# OTGW01_psu_rev1.net
KiCad netlist of a schematic drawn in Altium Designer
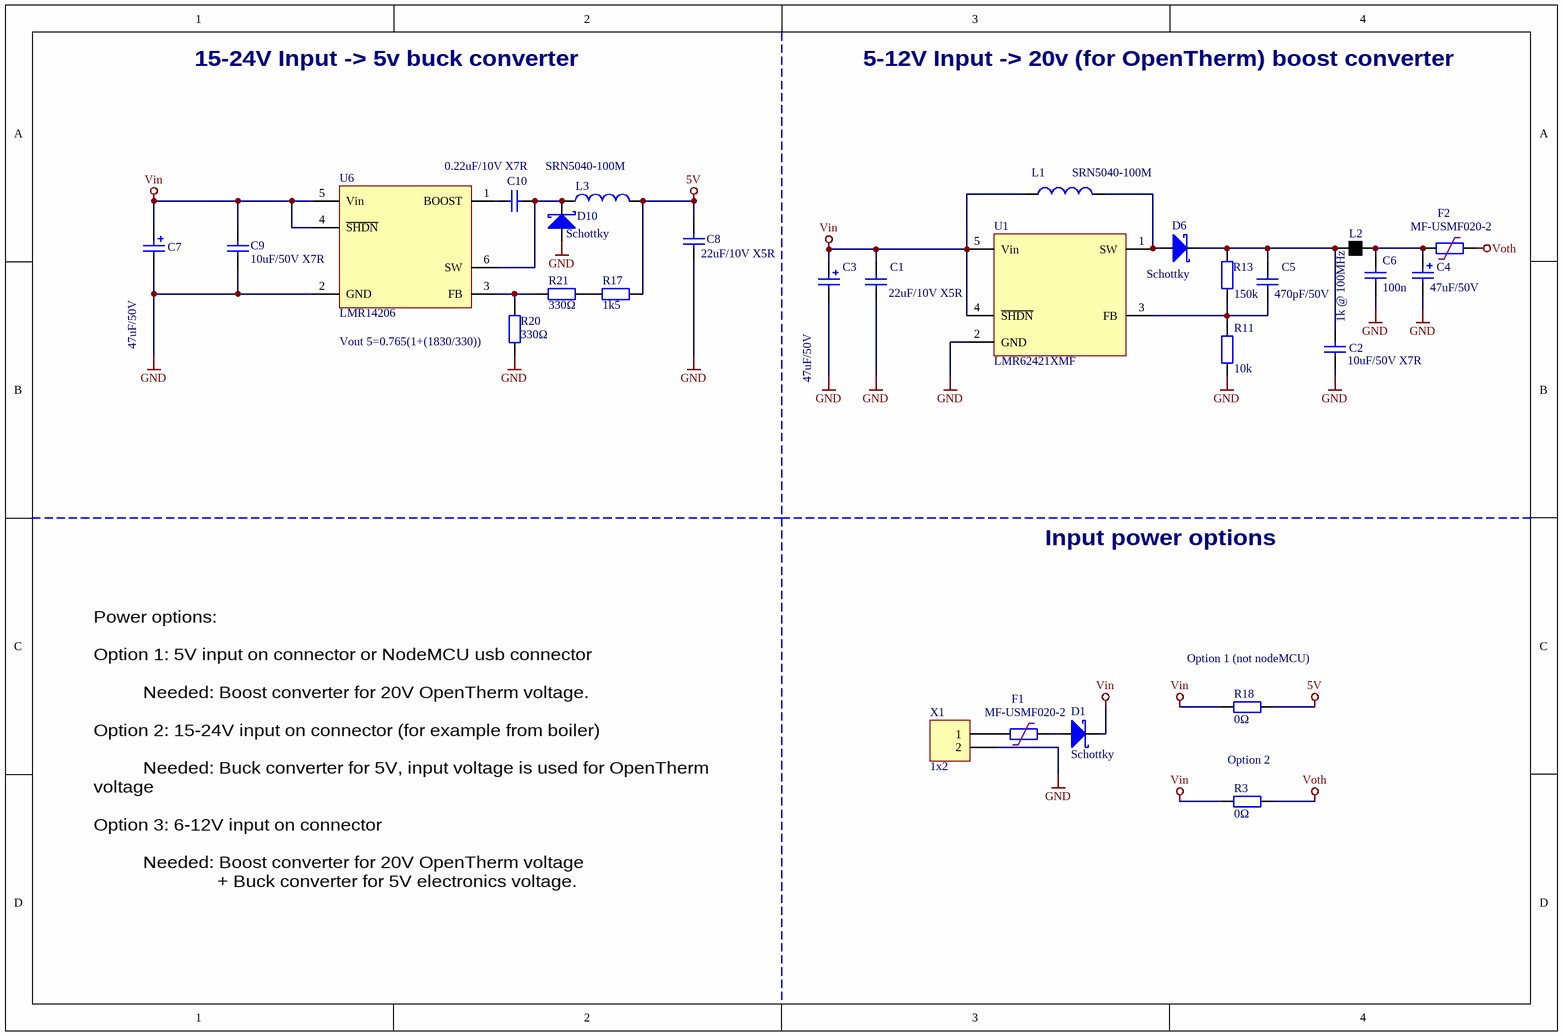
[diagram p0: OTGW01_psu_rev1.SchDoc]

(export (version "E")
  (design (tool "Eeschema 10.0.6"))
  (components
    (comp (ref "C1")
      (value "22uF/10V X5R")
      (footprint "1210")
      (description "Capacitor Non Polarized")
      (libsource (lib "OTGW01_rev1") (part "C"))
    )
    (comp (ref "C2")
      (value "10uF/50V X7R")
      (footprint "1210")
      (description "Capacitor Non Polarized")
      (libsource (lib "OTGW01_rev1") (part "C"))
    )
    (comp (ref "C3")
      (value "47uF/50V")
      (footprint "C_D8")
      (description "Capacitor Polarized")
      (libsource (lib "OTGW01_rev1") (part "C_POL"))
    )
    (comp (ref "C4")
      (value "47uF/50V")
      (footprint "C_D8")
      (description "Capacitor Polarized")
      (libsource (lib "OTGW01_rev1") (part "C_POL"))
    )
    (comp (ref "C5")
      (value "470pF/50V")
      (footprint "0805")
      (description "Capacitor Non Polarized")
      (libsource (lib "OTGW01_rev1") (part "C"))
    )
    (comp (ref "C6")
      (value "100n")
      (footprint "0805")
      (description "Capacitor Non Polarized")
      (libsource (lib "sap") (part "C"))
    )
    (comp (ref "C7")
      (value "47uF/50V")
      (footprint "C_D8")
      (description "Capacitor Polarized")
      (libsource (lib "OTGW01_rev1") (part "C_POL"))
    )
    (comp (ref "C8")
      (value "22uF/10V X5R")
      (footprint "1210")
      (description "Capacitor Non Polarized")
      (libsource (lib "OTGW01_rev1") (part "C"))
    )
    (comp (ref "C9")
      (value "10uF/50V X7R")
      (footprint "1210")
      (description "Capacitor Non Polarized")
      (libsource (lib "OTGW01_rev1") (part "C"))
    )
    (comp (ref "C10")
      (value "0.22uF/10V X7R")
      (footprint "0805")
      (description "Capacitor Non Polarized")
      (libsource (lib "OTGW01_rev1") (part "C"))
    )
    (comp (ref "D1") (value "Schottky") (footprint "SOD123") (libsource (lib "OTGW01_rev1") (part "D_S")))
    (comp (ref "D6") (value "Schottky") (footprint "SOD123") (libsource (lib "OTGW01_rev1") (part "D_S")))
    (comp (ref "D10") (value "Schottky") (footprint "SOD123") (libsource (lib "OTGW01_rev1") (part "D_S")))
    (comp (ref "F1") (value "MF-USMF020-2") (footprint "1210F") (libsource (lib "OTGW01_rev1") (part "PPTC")))
    (comp (ref "F2") (value "MF-USMF020-2") (footprint "1210F") (libsource (lib "OTGW01_rev1") (part "PPTC")))
    (comp (ref "L1")
      (value "SRN5040-100M")
      (footprint "SRN5040")
      (description "L")
      (libsource (lib "OTGW01_rev1") (part "L"))
    )
    (comp (ref "L2")
      (value "1k @ 100MHz")
      (footprint "0805")
      (libsource (lib "OTGW01_rev1") (part "Ferrite"))
    )
    (comp (ref "L3")
      (value "SRN5040-100M")
      (footprint "SRN5040")
      (description "L")
      (libsource (lib "OTGW01_rev1") (part "L"))
    )
    (comp (ref "R3")
      (value "0Ω")
      (footprint "0805")
      (description "Resistor")
      (libsource (lib "") (part "R_1"))
    )
    (comp (ref "R11")
      (value "10k")
      (footprint "0805")
      (description "Resistor")
      (libsource (lib "OTGW01_rev1") (part "R"))
    )
    (comp (ref "R13")
      (value "150k")
      (footprint "0805")
      (description "Resistor")
      (libsource (lib "OTGW01_rev1") (part "R"))
    )
    (comp (ref "R17")
      (value "1k5")
      (footprint "0805")
      (description "Resistor")
      (libsource (lib "") (part "R_1"))
    )
    (comp (ref "R18")
      (value "0Ω")
      (footprint "0805")
      (description "Resistor")
      (libsource (lib "") (part "R_1"))
    )
    (comp (ref "R20")
      (value "330Ω")
      (footprint "0805")
      (description "Resistor")
      (libsource (lib "") (part "R_2"))
    )
    (comp (ref "R21")
      (value "330Ω")
      (footprint "0805")
      (description "Resistor")
      (libsource (lib "") (part "R_1"))
    )
    (comp (ref "U1")
      (value "LMR62421XMF")
      (footprint "SOT23_5")
      (libsource (lib "OTGW01_rev1") (part "LMR62421XMF"))
    )
    (comp (ref "U6")
      (value "LMR14206")
      (footprint "SOT23_6")
      (libsource (lib "OTGW01_rev1") (part "LMR14206"))
    )
    (comp (ref "X1")
      (value "1x2")
      (footprint "Terminal_2x3.5mm")
      (libsource (lib "OTGW01_rev1") (part "CON_1x2"))
    )
  )
  (nets
    (net (code "1") (name "5V") (class "Default")
      (node (ref "C8") (pin "2") (pinfunction "2_2") (pintype "passive"))
      (node (ref "L3") (pin "2") (pinfunction "2_2") (pintype "passive"))
      (node (ref "R17") (pin "2") (pinfunction "2_2") (pintype "passive"))
      (node (ref "R18") (pin "2") (pinfunction "2_2") (pintype "passive"))
    )
    (net (code "2") (name "GND") (class "Default")
      (node (ref "C1") (pin "1") (pinfunction "1_1") (pintype "passive"))
      (node (ref "C2") (pin "2") (pinfunction "2_2") (pintype "passive"))
      (node (ref "C3") (pin "2") (pinfunction "2_2") (pintype "passive"))
      (node (ref "C4") (pin "2") (pinfunction "2_2") (pintype "passive"))
      (node (ref "C6") (pin "1") (pinfunction "1_1") (pintype "passive"))
      (node (ref "C7") (pin "2") (pinfunction "2_2") (pintype "passive"))
      (node (ref "C8") (pin "1") (pinfunction "1_1") (pintype "passive"))
      (node (ref "C9") (pin "1") (pinfunction "1_1") (pintype "passive"))
      (node (ref "D10") (pin "2") (pinfunction "2_2") (pintype "passive"))
      (node (ref "R11") (pin "2") (pinfunction "2_2") (pintype "passive"))
      (node (ref "R20") (pin "1") (pinfunction "1_1") (pintype "passive"))
      (node (ref "U1") (pin "2") (pinfunction "GND_2") (pintype "power_in"))
      (node (ref "U6") (pin "2") (pinfunction "GND_2") (pintype "power_in"))
      (node (ref "X1") (pin "2") (pinfunction "2_2") (pintype "passive"))
    )
    (net (code "3") (name "Net-(D1-Pad2)") (class "Default")
      (node (ref "D1") (pin "2") (pinfunction "2_2") (pintype "passive"))
      (node (ref "F1") (pin "2") (pinfunction "2_2") (pintype "passive"))
    )
    (net (code "4") (name "Net-(F1-Pad1)") (class "Default")
      (node (ref "F1") (pin "1") (pinfunction "1_1") (pintype "passive"))
      (node (ref "X1") (pin "1") (pinfunction "1_1") (pintype "passive"))
    )
    (net (code "5") (name "Net-(L2-IN)") (class "Default")
      (node (ref "C4") (pin "1") (pinfunction "1_1") (pintype "passive"))
      (node (ref "C6") (pin "2") (pinfunction "2_2") (pintype "passive"))
      (node (ref "F2") (pin "1") (pinfunction "1_1") (pintype "passive"))
      (node (ref "L2") (pin "1") (pinfunction "IN_1") (pintype "passive"))
    )
    (net (code "6") (name "Net-(L2-OUT)") (class "Default")
      (node (ref "C2") (pin "1") (pinfunction "1_1") (pintype "passive"))
      (node (ref "C5") (pin "1") (pinfunction "1_1") (pintype "passive"))
      (node (ref "D6") (pin "1") (pinfunction "1_1") (pintype "passive"))
      (node (ref "L2") (pin "2") (pinfunction "OUT_2") (pintype "passive"))
      (node (ref "R13") (pin "1") (pinfunction "1_1") (pintype "passive"))
    )
    (net (code "7") (name "Net-(R17-Pad1)") (class "Default")
      (node (ref "R17") (pin "1") (pinfunction "1_1") (pintype "passive"))
      (node (ref "R21") (pin "2") (pinfunction "2_2") (pintype "passive"))
    )
    (net (code "8") (name "Net-(U1-FB)") (class "Default")
      (node (ref "C5") (pin "2") (pinfunction "2_2") (pintype "passive"))
      (node (ref "R11") (pin "1") (pinfunction "1_1") (pintype "passive"))
      (node (ref "R13") (pin "2") (pinfunction "2_2") (pintype "passive"))
      (node (ref "U1") (pin "3") (pinfunction "FB_3") (pintype "passive"))
    )
    (net (code "9") (name "Net-(U1-SW)") (class "Default")
      (node (ref "D6") (pin "2") (pinfunction "2_2") (pintype "passive"))
      (node (ref "L1") (pin "2") (pinfunction "2_2") (pintype "passive"))
      (node (ref "U1") (pin "1") (pinfunction "SW_1") (pintype "passive"))
    )
    (net (code "10") (name "Net-(U6-BOOST)") (class "Default")
      (node (ref "C10") (pin "2") (pinfunction "2_2") (pintype "passive"))
      (node (ref "U6") (pin "1") (pinfunction "BOOST_1") (pintype "passive"))
    )
    (net (code "11") (name "Net-(U6-FB)") (class "Default")
      (node (ref "R20") (pin "2") (pinfunction "2_2") (pintype "passive"))
      (node (ref "R21") (pin "1") (pinfunction "1_1") (pintype "passive"))
      (node (ref "U6") (pin "3") (pinfunction "FB_3") (pintype "passive"))
    )
    (net (code "12") (name "Net-(U6-SW)") (class "Default")
      (node (ref "C10") (pin "1") (pinfunction "1_1") (pintype "passive"))
      (node (ref "D10") (pin "1") (pinfunction "1_1") (pintype "passive"))
      (node (ref "L3") (pin "1") (pinfunction "1_1") (pintype "passive"))
      (node (ref "U6") (pin "6") (pinfunction "SW_6") (pintype "passive"))
    )
    (net (code "13") (name "Vin") (class "Default")
      (node (ref "C1") (pin "2") (pinfunction "2_2") (pintype "passive"))
      (node (ref "C3") (pin "1") (pinfunction "1_1") (pintype "passive"))
      (node (ref "C7") (pin "1") (pinfunction "1_1") (pintype "passive"))
      (node (ref "C9") (pin "2") (pinfunction "2_2") (pintype "passive"))
      (node (ref "D1") (pin "1") (pinfunction "1_1") (pintype "passive"))
      (node (ref "L1") (pin "1") (pinfunction "1_1") (pintype "passive"))
      (node (ref "R18") (pin "1") (pinfunction "1_1") (pintype "passive"))
      (node (ref "R3") (pin "1") (pinfunction "1_1") (pintype "passive"))
      (node (ref "U1") (pin "4") (pinfunction "~{SHDN}_4") (pintype "passive"))
      (node (ref "U1") (pin "5") (pinfunction "Vin_5") (pintype "passive"))
      (node (ref "U6") (pin "4") (pinfunction "~{SHDN}_4") (pintype "passive"))
      (node (ref "U6") (pin "5") (pinfunction "Vin_5") (pintype "passive"))
    )
    (net (code "14") (name "Voth") (class "Default")
      (node (ref "F2") (pin "2") (pinfunction "2_2") (pintype "passive"))
      (node (ref "R3") (pin "2") (pinfunction "2_2") (pintype "passive"))
    )
  )
)
